# OSO-SCAP-A1-01.net
KiCad netlist of a schematic drawn in EAGLE
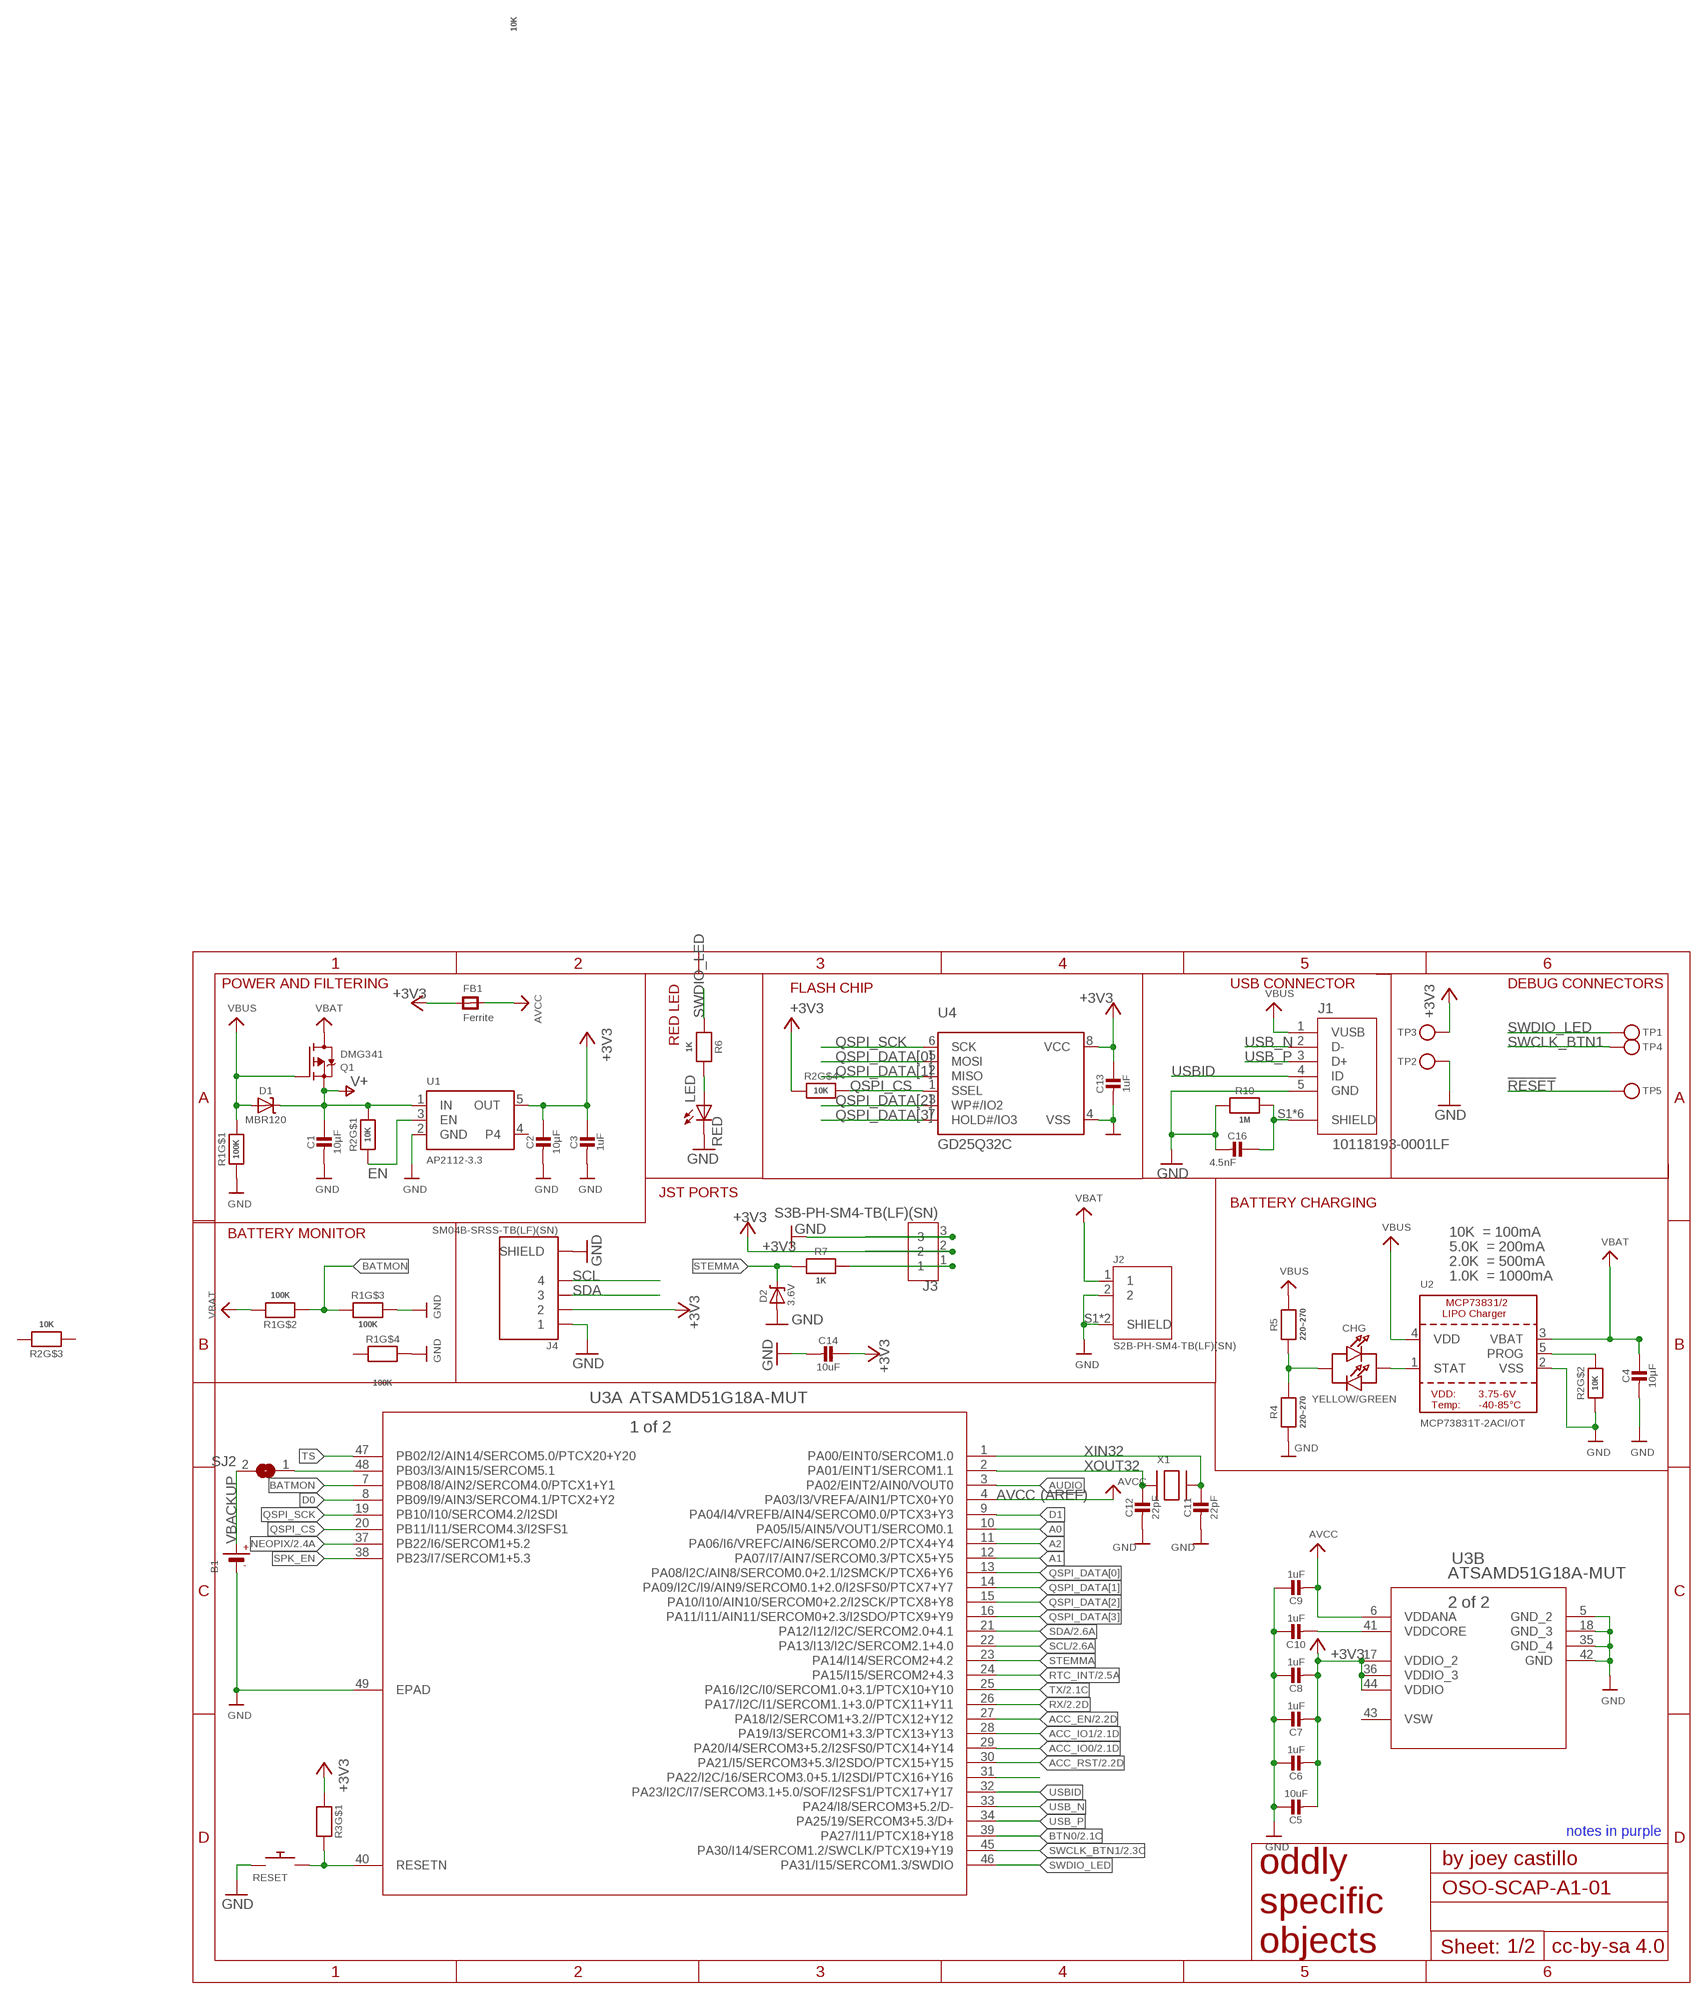
[diagram p0: schematic, sheet 1]
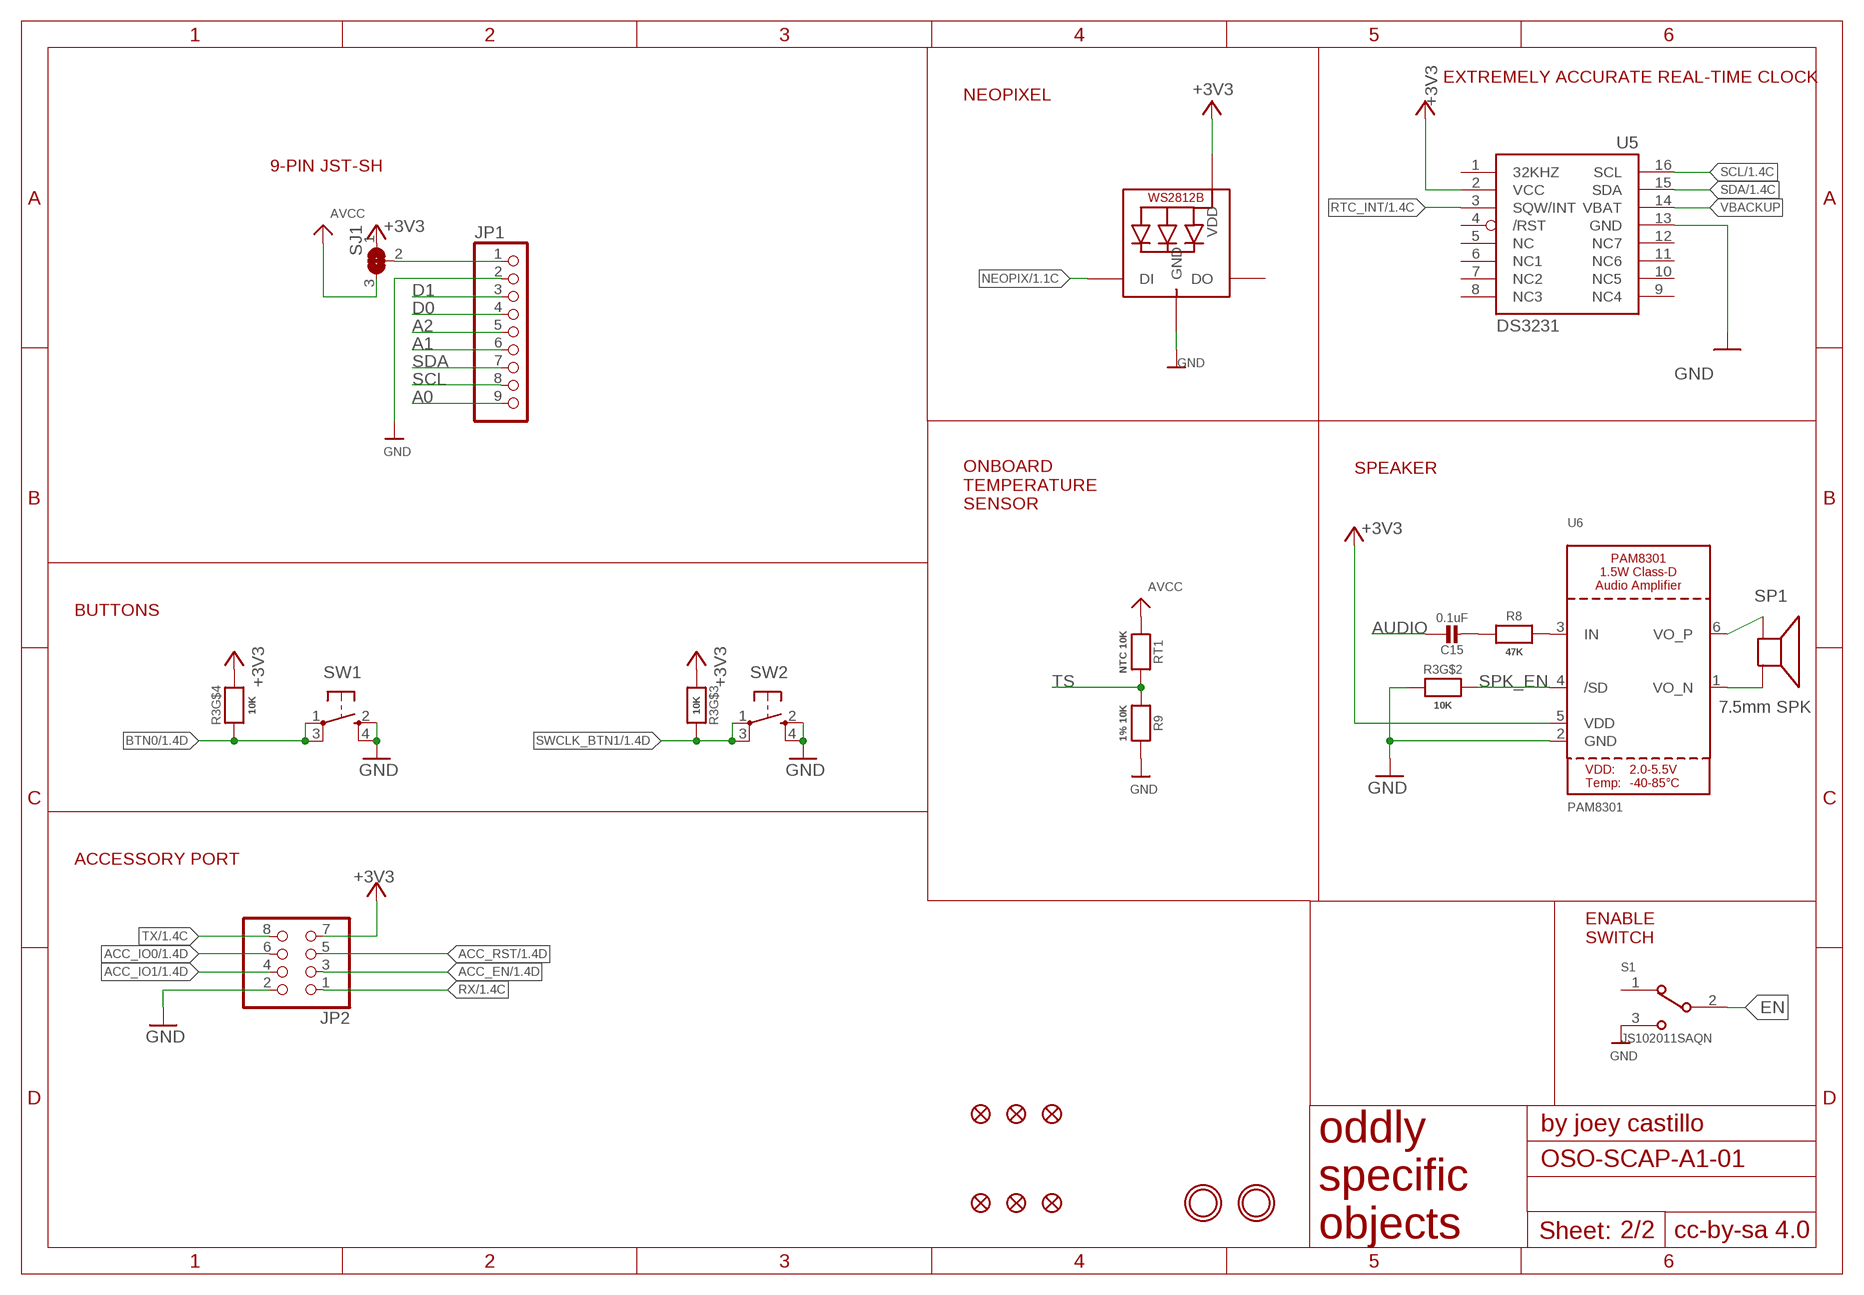
[diagram p1: schematic, sheet 2]

(export (version "E")
  (design (tool "Eeschema 10.0.6"))
  (components
    (comp (ref "C15")
      (value "0.1uF")
      (footprint "eagle-import:0805-NO")
      (libsource (lib "eagle-import") (part "CAP_CERAMIC0805-NOOUTLINE"))
    )
    (comp (ref "FID1")
      (value "FIDUCIAL_1MM")
      (footprint "eagle-import:FIDUCIAL_1MM")
      (libsource (lib "eagle-import") (part "FIDUCIAL_1MM"))
    )
    (comp (ref "FID2")
      (value "FIDUCIAL_1MM")
      (footprint "eagle-import:FIDUCIAL_1MM")
      (libsource (lib "eagle-import") (part "FIDUCIAL_1MM"))
    )
    (comp (ref "FID3")
      (value "FIDUCIAL_1MM")
      (footprint "eagle-import:FIDUCIAL_1MM")
      (libsource (lib "eagle-import") (part "FIDUCIAL_1MM"))
    )
    (comp (ref "FID4")
      (value "FIDUCIAL_1MM")
      (footprint "eagle-import:FIDUCIAL_1MM")
      (libsource (lib "eagle-import") (part "FIDUCIAL_1MM"))
    )
    (comp (ref "FID5")
      (value "FIDUCIAL_1MM")
      (footprint "eagle-import:FIDUCIAL_1MM")
      (libsource (lib "eagle-import") (part "FIDUCIAL_1MM"))
    )
    (comp (ref "FID6")
      (value "FIDUCIAL_1MM")
      (footprint "eagle-import:FIDUCIAL_1MM")
      (libsource (lib "eagle-import") (part "FIDUCIAL_1MM"))
    )
    (comp (ref "JP1")
      (value "HEADER-1X9_JSTSH")
      (footprint "eagle-import:JST_SH9")
      (libsource (lib "eagle-import") (part "HEADER-1X9_JSTSH"))
    )
    (comp (ref "JP2")
      (value "PINHD-2X4SMT")
      (footprint "eagle-import:PINHD_2X4_SMT")
      (libsource (lib "eagle-import") (part "PINHD-2X4SMT"))
    )
    (comp (ref "NEOPIX")
      (value "WS2812B_4020")
      (footprint "eagle-import:WS2812B_4020")
      (libsource (lib "eagle-import") (part "WS2812B_4020"))
    )
    (comp (ref "R3")
      (value "10K")
      (footprint "eagle-import:EXBV8V")
      (fields (field (name "MANUFACTURER_PART_NUMBER") "EXBV8V103JV"))
      (libsource (lib "eagle-import") (part "EXB-V8V103JV-GOOD"))
    )
    (comp (ref "R8")
      (value "47K")
      (footprint "eagle-import:0805-NO")
      (libsource (lib "eagle-import") (part "RESISTOR0805_NOOUTLINE"))
    )
    (comp (ref "R9")
      (value "1% 10K")
      (footprint "eagle-import:0805-NO")
      (libsource (lib "eagle-import") (part "RESISTOR0805_NOOUTLINE"))
    )
    (comp (ref "RT1")
      (value "NTC 10K")
      (footprint "eagle-import:0805-NO")
      (libsource (lib "eagle-import") (part "RESISTOR0805_NOOUTLINE"))
    )
    (comp (ref "S1")
      (value "JS102011SAQN")
      (footprint "eagle-import:SW_JS102011SAQN")
      (fields (field (name "DIGI-KEY_PART_NUMBER") "401-1999-1-ND") (field (name "MF") "C&K"))
      (libsource (lib "eagle-import") (part "JS102011SAQN"))
    )
    (comp (ref "SJ1")
      (value "SOLDERJUMPER_2WAY")
      (footprint "eagle-import:SOLDERJUMPER_2WAY_OPEN_NOPASTE")
      (libsource (lib "eagle-import") (part "SOLDERJUMPER_2WAY"))
    )
    (comp (ref "SP1")
      (value "7.5mm SPK")
      (footprint "eagle-import:BUZZER_SMT_5MM")
      (libsource (lib "eagle-import") (part "SPEAKER_BUZZER5MM"))
    )
    (comp (ref "SW1")
      (value "SPST_TACT-KMR2")
      (footprint "eagle-import:KMR2")
      (libsource (lib "eagle-import") (part "SPST_TACT-KMR2"))
    )
    (comp (ref "SW2")
      (value "SPST_TACT-KMR2")
      (footprint "eagle-import:KMR2")
      (libsource (lib "eagle-import") (part "SPST_TACT-KMR2"))
    )
    (comp (ref "U$1")
      (value "MOUNTINGHOLE2.5")
      (footprint "eagle-import:MOUNTINGHOLE_2.5_PLATED")
      (libsource (lib "eagle-import") (part "MOUNTINGHOLE2.5"))
    )
    (comp (ref "U$4")
      (value "MOUNTINGHOLE2.5")
      (footprint "eagle-import:MOUNTINGHOLE_2.5_PLATED")
      (libsource (lib "eagle-import") (part "MOUNTINGHOLE2.5"))
    )
    (comp (ref "U5")
      (value "DS3231/SO")
      (footprint "eagle-import:SO16W")
      (libsource (lib "eagle-import") (part "DS3231/SO"))
    )
    (comp (ref "U6")
      (value "PAM8301")
      (footprint "eagle-import:SOT23-6")
      (libsource (lib "eagle-import") (part "PAM8301"))
    )
    (comp (ref "B1")
      (value "CR1220")
      (footprint "eagle-import:CR1220-2")
      (libsource (lib "eagle-import") (part "BATTERYCR1220_2"))
    )
    (comp (ref "C1")
      (value "10µF")
      (footprint "eagle-import:0805-NO")
      (libsource (lib "eagle-import") (part "CAP_CERAMIC0805-NOOUTLINE"))
    )
    (comp (ref "C2")
      (value "10µF")
      (footprint "eagle-import:0805-NO")
      (libsource (lib "eagle-import") (part "CAP_CERAMIC0805-NOOUTLINE"))
    )
    (comp (ref "C3")
      (value "1uF")
      (footprint "eagle-import:0805-NO")
      (libsource (lib "eagle-import") (part "CAP_CERAMIC0805-NOOUTLINE"))
    )
    (comp (ref "C4")
      (value "10µF")
      (footprint "eagle-import:0805-NO")
      (libsource (lib "eagle-import") (part "CAP_CERAMIC0805-NOOUTLINE"))
    )
    (comp (ref "C5")
      (value "10uF")
      (footprint "eagle-import:0805_10MGAP")
      (libsource (lib "eagle-import") (part "CAP_CERAMIC0805_10MGAP"))
    )
    (comp (ref "C6")
      (value "1uF")
      (footprint "eagle-import:0805-NO")
      (libsource (lib "eagle-import") (part "CAP_CERAMIC0805-NOOUTLINE"))
    )
    (comp (ref "C7")
      (value "1uF")
      (footprint "eagle-import:0805-NO")
      (libsource (lib "eagle-import") (part "CAP_CERAMIC0805-NOOUTLINE"))
    )
    (comp (ref "C8")
      (value "1uF")
      (footprint "eagle-import:0805-NO")
      (libsource (lib "eagle-import") (part "CAP_CERAMIC0805-NOOUTLINE"))
    )
    (comp (ref "C9")
      (value "1uF")
      (footprint "eagle-import:0805_10MGAP")
      (libsource (lib "eagle-import") (part "CAP_CERAMIC0805_10MGAP"))
    )
    (comp (ref "C10")
      (value "1uF")
      (footprint "eagle-import:0805_10MGAP")
      (libsource (lib "eagle-import") (part "CAP_CERAMIC0805_10MGAP"))
    )
    (comp (ref "C11")
      (value "22pF")
      (footprint "eagle-import:0805-NO")
      (libsource (lib "eagle-import") (part "CAP_CERAMIC0805-NOOUTLINE"))
    )
    (comp (ref "C12")
      (value "22pF")
      (footprint "eagle-import:0805-NO")
      (libsource (lib "eagle-import") (part "CAP_CERAMIC0805-NOOUTLINE"))
    )
    (comp (ref "C13")
      (value "1uF")
      (footprint "eagle-import:0805-NO")
      (libsource (lib "eagle-import") (part "CAP_CERAMIC0805-NOOUTLINE"))
    )
    (comp (ref "C14")
      (value "10uF")
      (footprint "eagle-import:0805-NO")
      (libsource (lib "eagle-import") (part "CAP_CERAMIC0805-NOOUTLINE"))
    )
    (comp (ref "C16")
      (value "4.5nF")
      (footprint "eagle-import:0805-NO")
      (libsource (lib "eagle-import") (part "CAP_CERAMIC0805-NOOUTLINE"))
    )
    (comp (ref "CHG")
      (value "YELLOW/GREEN")
      (footprint "eagle-import:CHIPLED_1206")
      (libsource (lib "eagle-import") (part "LED_BIDI1206"))
    )
    (comp (ref "D1")
      (value "MBR120")
      (footprint "eagle-import:SOD-123")
      (libsource (lib "eagle-import") (part "DIODE-SCHOTTKYSOD-123"))
    )
    (comp (ref "D2")
      (value "3.6V")
      (footprint "eagle-import:SOD-123")
      (libsource (lib "eagle-import") (part "DIODE-ZENERSOD123"))
    )
    (comp (ref "FB1")
      (value "Ferrite")
      (footprint "eagle-import:_0805MP")
      (libsource (lib "eagle-import") (part "FERRITE_0805MP"))
    )
    (comp (ref "J1")
      (value "10118193-0001LF")
      (footprint "eagle-import:FCI_10118193-0001LF")
      (fields (field (name "DIGI-KEY_PART_NUMBER") "609-4616-1-ND") (field (name "MF") "Amphenol ICC"))
      (libsource (lib "eagle-import") (part "10118193-0001LF"))
    )
    (comp (ref "J2")
      (value "S2B-PH-SM4-TB(LF)(SN)")
      (footprint "eagle-import:JST_S2B-PH-SM4-TB(LF)(SN)")
      (fields
        (field (name "DIGI-KEY_PART_NUMBER") "455-1749-1-ND")
        (field (name "MF") "JST Sales")
        (field (name "MP") "S2B-PH-SM4-TB_LF__SN_")
      )
      (libsource (lib "eagle-import") (part "S2B-PH-SM4-TB(LF)(SN)"))
    )
    (comp (ref "J3")
      (value "S3B-PH-SM4-TB(LF)(SN)")
      (footprint "eagle-import:JST_S3B-PH-SM4-TB(LF)(SN)")
      (fields
        (field (name "DIGI-KEY_PART_NUMBER") "455-1750-1-ND")
        (field (name "MF") "JST Sales")
        (field (name "MP") "S3B-PH-SM4-TB_LF__SN_")
      )
      (libsource (lib "eagle-import") (part "S3B-PH-SM4-TB(LF)(SN)"))
    )
    (comp (ref "J4")
      (value "SM04B-SRSS-TB(LF)(SN)")
      (footprint "eagle-import:JST_SM04B-SRSS-TB(LF)(SN)")
      (fields
        (field (name "DIGI-KEY_PART_NUMBER") "455-1804-1-ND")
        (field (name "MF") "JST Sales")
        (field (name "MP") "SM04B-SRSS-TB_LF__SN_")
      )
      (libsource (lib "eagle-import") (part "SM04B-SRSS-TB(LF)(SN)"))
    )
    (comp (ref "LED")
      (value "RED")
      (footprint "eagle-import:CHIPLED_1206")
      (libsource (lib "eagle-import") (part "LEDCHIPLED_1206"))
    )
    (comp (ref "Q1")
      (value "DMG341")
      (footprint "eagle-import:SOT23-R")
      (libsource (lib "eagle-import") (part "MOSFET-P"))
    )
    (comp (ref "R1")
      (value "100K")
      (footprint "eagle-import:EXBV8V")
      (fields (field (name "MANUFACTURER_PART_NUMBER") "EXBV8V103JV"))
      (libsource (lib "eagle-import") (part "EXB-V8V103JV-GOOD"))
    )
    (comp (ref "R2")
      (value "10K")
      (footprint "eagle-import:EXBV8V")
      (fields (field (name "MANUFACTURER_PART_NUMBER") "EXBV8V103JV"))
      (libsource (lib "eagle-import") (part "EXB-V8V103JV-GOOD"))
    )
    (comp (ref "R4")
      (value "220~270")
      (footprint "eagle-import:0805-NO")
      (libsource (lib "eagle-import") (part "RESISTOR0805_NOOUTLINE"))
    )
    (comp (ref "R5")
      (value "220~270")
      (footprint "eagle-import:0805-NO")
      (libsource (lib "eagle-import") (part "RESISTOR0805_NOOUTLINE"))
    )
    (comp (ref "R6")
      (value "1K")
      (footprint "eagle-import:0805-NO")
      (libsource (lib "eagle-import") (part "RESISTOR0805_NOOUTLINE"))
    )
    (comp (ref "R7")
      (value "1K")
      (footprint "eagle-import:0805-NO")
      (libsource (lib "eagle-import") (part "RESISTOR0805_NOOUTLINE"))
    )
    (comp (ref "R10")
      (value "1M")
      (footprint "eagle-import:0805-NO")
      (libsource (lib "eagle-import") (part "RESISTOR0805_NOOUTLINE"))
    )
    (comp (ref "RESET")
      (value "SWITCH_PUSHBUTTONC&K_KSS")
      (footprint "eagle-import:BTN_CK_KSS")
      (libsource (lib "eagle-import") (part "SWITCH_PUSHBUTTONC&K_KSS"))
    )
    (comp (ref "SJ2")
      (value "SOLDERJUMPERREFLOW_NOPASTE")
      (footprint "eagle-import:SOLDERJUMPER_REFLOW_NOPASTE")
      (libsource (lib "eagle-import") (part "SOLDERJUMPERREFLOW_NOPASTE"))
    )
    (comp (ref "TP1")
      (value "TESTPOINTROUND1.5MMNO")
      (footprint "eagle-import:TESTPOINT_ROUND_1.5MM_NO")
      (libsource (lib "eagle-import") (part "TESTPOINTROUND1.5MMNO"))
    )
    (comp (ref "TP2")
      (value "TESTPOINTROUND1.5MMNO")
      (footprint "eagle-import:TESTPOINT_ROUND_1.5MM_NO")
      (libsource (lib "eagle-import") (part "TESTPOINTROUND1.5MMNO"))
    )
    (comp (ref "TP3")
      (value "TESTPOINTROUND1.5MMNO")
      (footprint "eagle-import:TESTPOINT_ROUND_1.5MM_NO")
      (libsource (lib "eagle-import") (part "TESTPOINTROUND1.5MMNO"))
    )
    (comp (ref "TP4")
      (value "TESTPOINTROUND1.5MMNO")
      (footprint "eagle-import:TESTPOINT_ROUND_1.5MM_NO")
      (libsource (lib "eagle-import") (part "TESTPOINTROUND1.5MMNO"))
    )
    (comp (ref "TP5")
      (value "TESTPOINTROUND1.5MMNO")
      (footprint "eagle-import:TESTPOINT_ROUND_1.5MM_NO")
      (libsource (lib "eagle-import") (part "TESTPOINTROUND1.5MMNO"))
    )
    (comp (ref "U1")
      (value "AP2112-3.3")
      (footprint "eagle-import:SOT23-5")
      (libsource (lib "eagle-import") (part "VREG_SOT23-5"))
    )
    (comp (ref "U2")
      (value "MCP73831T-2ACI/OT")
      (footprint "eagle-import:SOT23-5")
      (libsource (lib "eagle-import") (part "MCP73831/2"))
    )
    (comp (ref "U3")
      (value "ATSAMD51G18A-MUT")
      (footprint "eagle-import:QFN48_7X7MC")
      (fields (field (name "COPYRIGHT") "Copyright (C) 2018 Accelerated Designs. All rights reserved"))
      (libsource (lib "eagle-import") (part "ATSAMD51G18A-MUT"))
    )
    (comp (ref "U4")
      (value "GD25Q32C")
      (footprint "eagle-import:MICROBUILDER_SOIC8_150MIL")
      (libsource (lib "eagle-import") (part "MICROBUILDER_SPIFLASH_SOIC8"))
    )
    (comp (ref "X1")
      (value "XTAL-3.2X1.5")
      (footprint "eagle-import:XTAL3215")
      (libsource (lib "eagle-import") (part "XTAL-3.2X1.5"))
    )
  )
  (nets
    (net (code "1") (name "+3V3") (class "Default")
      (node (ref "C13") (pin "1") (pinfunction "1_1") (pintype "passive"))
      (node (ref "C14") (pin "1") (pinfunction "1_1") (pintype "passive"))
      (node (ref "C2") (pin "1") (pinfunction "1_1") (pintype "passive"))
      (node (ref "C3") (pin "1") (pinfunction "1_1") (pintype "passive"))
      (node (ref "C5") (pin "2") (pinfunction "2_2") (pintype "passive"))
      (node (ref "C6") (pin "2") (pinfunction "2_2") (pintype "passive"))
      (node (ref "C7") (pin "2") (pinfunction "2_2") (pintype "passive"))
      (node (ref "C8") (pin "2") (pinfunction "2_2") (pintype "passive"))
      (node (ref "FB1") (pin "1") (pinfunction "P$1_1") (pintype "passive"))
      (node (ref "J3") (pin "2") (pinfunction "2_2") (pintype "passive"))
      (node (ref "J4") (pin "2") (pinfunction "2_2") (pintype "passive"))
      (node (ref "JP2") (pin "7") (pinfunction "7_7") (pintype "passive"))
      (node (ref "NEOPIX") (pin "2") (pinfunction "VDD_2") (pintype "power_in"))
      (node (ref "R2") (pin "4") (pinfunction "1_4") (pintype "passive"))
      (node (ref "R3") (pin "1") (pinfunction "1_1") (pintype "passive"))
      (node (ref "R3") (pin "3") (pinfunction "1_3") (pintype "passive"))
      (node (ref "R3") (pin "5") (pinfunction "2_5") (pintype "passive"))
      (node (ref "SJ1") (pin "1") (pinfunction "1_1") (pintype "passive"))
      (node (ref "TP3") (pin "P$1") (pinfunction "P$1_P$1") (pintype "bidirectional"))
      (node (ref "U1") (pin "5") (pinfunction "OUT_5") (pintype "power_in"))
      (node (ref "U3") (pin "17") (pinfunction "VDDIO_2_17") (pintype "power_in"))
      (node (ref "U3") (pin "36") (pinfunction "VDDIO_3_36") (pintype "power_in"))
      (node (ref "U3") (pin "44") (pinfunction "VDDIO_44") (pintype "power_in"))
      (node (ref "U4") (pin "8") (pinfunction "VCC_8") (pintype "bidirectional"))
      (node (ref "U5") (pin "2") (pinfunction "VCC_2") (pintype "power_in"))
      (node (ref "U6") (pin "5") (pinfunction "VDD_5") (pintype "power_in"))
    )
    (net (code "2") (name "A0") (class "Default")
      (node (ref "JP1") (pin "9") (pinfunction "9_9") (pintype "passive"))
      (node (ref "U3") (pin "10") (pinfunction "PA05/I5/AIN5/VOUT1/SERCOM0.1_10") (pintype "bidirectional"))
    )
    (net (code "3") (name "A1") (class "Default")
      (node (ref "JP1") (pin "6") (pinfunction "6_6") (pintype "passive"))
      (node (ref "U3") (pin "12") (pinfunction "PA07/I7/AIN7/SERCOM0.3/PTCX5+Y5_12") (pintype "bidirectional"))
    )
    (net (code "4") (name "A2") (class "Default")
      (node (ref "JP1") (pin "5") (pinfunction "5_5") (pintype "passive"))
      (node (ref "U3") (pin "11") (pinfunction "PA06/I6/VREFC/AIN6/SERCOM0.2/PTCX4+Y4_11") (pintype "bidirectional"))
    )
    (net (code "5") (name "ACC_EN") (class "Default")
      (node (ref "JP2") (pin "3") (pinfunction "3_3") (pintype "passive"))
      (node (ref "U3") (pin "27") (pinfunction "PA18/I2/SERCOM1+3.2//PTCX12+Y12_27") (pintype "bidirectional"))
    )
    (net (code "6") (name "ACC_IO0") (class "Default")
      (node (ref "JP2") (pin "6") (pinfunction "6_6") (pintype "passive"))
      (node (ref "U3") (pin "29") (pinfunction "PA20/I4/SERCOM3+5.2/I2SFS0/PTCX14+Y14_29") (pintype "bidirectional"))
    )
    (net (code "7") (name "ACC_IO1") (class "Default")
      (node (ref "JP2") (pin "4") (pinfunction "4_4") (pintype "passive"))
      (node (ref "U3") (pin "28") (pinfunction "PA19/I3/SERCOM1+3.3/PTCX13+Y13_28") (pintype "bidirectional"))
    )
    (net (code "8") (name "ACC_RST") (class "Default")
      (node (ref "JP2") (pin "5") (pinfunction "5_5") (pintype "passive"))
      (node (ref "U3") (pin "30") (pinfunction "PA21/I5/SERCOM3+5.3/I2SDO/PTCX15+Y15_30") (pintype "bidirectional"))
    )
    (net (code "9") (name "AUDIO") (class "Default")
      (node (ref "C15") (pin "1") (pinfunction "1_1") (pintype "passive"))
      (node (ref "U3") (pin "3") (pinfunction "PA02/EINT2/AIN0/VOUT0_3") (pintype "bidirectional"))
    )
    (net (code "10") (name "AVCC") (class "Default")
      (node (ref "C9") (pin "2") (pinfunction "2_2") (pintype "passive"))
      (node (ref "FB1") (pin "2") (pinfunction "P$2_2") (pintype "passive"))
      (node (ref "RT1") (pin "1") (pinfunction "1_1") (pintype "passive"))
      (node (ref "SJ1") (pin "3") (pinfunction "3_3") (pintype "passive"))
      (node (ref "U3") (pin "4") (pinfunction "PA03/I3/VREFA/AIN1/PTCX0+Y0_4") (pintype "bidirectional"))
      (node (ref "U3") (pin "6") (pinfunction "VDDANA_6") (pintype "power_in"))
    )
    (net (code "11") (name "BATMON") (class "Default")
      (node (ref "R1") (pin "2") (pinfunction "1_2") (pintype "passive"))
      (node (ref "R1") (pin "3") (pinfunction "1_3") (pintype "passive"))
      (node (ref "U3") (pin "7") (pinfunction "PB08/I8/AIN2/SERCOM4.0/PTCX1+Y1_7") (pintype "bidirectional"))
    )
    (net (code "12") (name "BTN0") (class "Default")
      (node (ref "R3") (pin "4") (pinfunction "1_4") (pintype "passive"))
      (node (ref "SW1") (pin "1") (pinfunction "P_1") (pintype "passive"))
      (node (ref "SW1") (pin "3") (pinfunction "P1_3") (pintype "passive"))
      (node (ref "U3") (pin "39") (pinfunction "PA27/I11/PTCX18+Y18_39") (pintype "bidirectional"))
    )
    (net (code "13") (name "D0") (class "Default")
      (node (ref "JP1") (pin "4") (pinfunction "4_4") (pintype "passive"))
      (node (ref "U3") (pin "8") (pinfunction "PB09/I9/AIN3/SERCOM4.1/PTCX2+Y2_8") (pintype "bidirectional"))
    )
    (net (code "14") (name "D1") (class "Default")
      (node (ref "JP1") (pin "3") (pinfunction "3_3") (pintype "passive"))
      (node (ref "U3") (pin "9") (pinfunction "PA04/I4/VREFB/AIN4/SERCOM0.0/PTCX3+Y3_9") (pintype "bidirectional"))
    )
    (net (code "15") (name "EN") (class "Default")
      (node (ref "R2") (pin "1") (pinfunction "1_1") (pintype "passive"))
      (node (ref "S1") (pin "2") (pinfunction "2_2") (pintype "passive"))
      (node (ref "U1") (pin "3") (pinfunction "EN_3") (pintype "input"))
    )
    (net (code "16") (name "GND") (class "Default")
      (node (ref "B1") (pin "-") (pinfunction "-_-") (pintype "passive"))
      (node (ref "C1") (pin "2") (pinfunction "2_2") (pintype "passive"))
      (node (ref "C10") (pin "1") (pinfunction "1_1") (pintype "passive"))
      (node (ref "C11") (pin "2") (pinfunction "2_2") (pintype "passive"))
      (node (ref "C12") (pin "2") (pinfunction "2_2") (pintype "passive"))
      (node (ref "C13") (pin "2") (pinfunction "2_2") (pintype "passive"))
      (node (ref "C14") (pin "2") (pinfunction "2_2") (pintype "passive"))
      (node (ref "C16") (pin "2") (pinfunction "2_2") (pintype "passive"))
      (node (ref "C2") (pin "2") (pinfunction "2_2") (pintype "passive"))
      (node (ref "C3") (pin "2") (pinfunction "2_2") (pintype "passive"))
      (node (ref "C4") (pin "2") (pinfunction "2_2") (pintype "passive"))
      (node (ref "C5") (pin "1") (pinfunction "1_1") (pintype "passive"))
      (node (ref "C6") (pin "1") (pinfunction "1_1") (pintype "passive"))
      (node (ref "C7") (pin "1") (pinfunction "1_1") (pintype "passive"))
      (node (ref "C8") (pin "1") (pinfunction "1_1") (pintype "passive"))
      (node (ref "C9") (pin "1") (pinfunction "1_1") (pintype "passive"))
      (node (ref "D2") (pin "A") (pinfunction "A_A") (pintype "passive"))
      (node (ref "J1") (pin "5") (pinfunction "GND_5") (pintype "passive"))
      (node (ref "J2") (pin "2") (pinfunction "2_2") (pintype "passive"))
      (node (ref "J2") (pin "S1") (pinfunction "SHIELD_S1") (pintype "passive"))
      (node (ref "J2") (pin "S2") (pinfunction "SHIELD_S2") (pintype "passive"))
      (node (ref "J3") (pin "3") (pinfunction "3_3") (pintype "passive"))
      (node (ref "J4") (pin "1") (pinfunction "1_1") (pintype "passive"))
      (node (ref "J4") (pin "S1") (pinfunction "SHIELD_S1") (pintype "passive"))
      (node (ref "J4") (pin "S2") (pinfunction "SHIELD_S2") (pintype "passive"))
      (node (ref "JP1") (pin "2") (pinfunction "2_2") (pintype "passive"))
      (node (ref "JP2") (pin "2") (pinfunction "2_2") (pintype "passive"))
      (node (ref "LED") (pin "C") (pinfunction "C_C") (pintype "passive"))
      (node (ref "NEOPIX") (pin "4") (pinfunction "GND_4") (pintype "power_in"))
      (node (ref "R1") (pin "1") (pinfunction "1_1") (pintype "passive"))
      (node (ref "R1") (pin "5") (pinfunction "2_5") (pintype "passive"))
      (node (ref "R1") (pin "6") (pinfunction "2_6") (pintype "passive"))
      (node (ref "R10") (pin "2") (pinfunction "2_2") (pintype "passive"))
      (node (ref "R2") (pin "2") (pinfunction "1_2") (pintype "passive"))
      (node (ref "R3") (pin "2") (pinfunction "1_2") (pintype "passive"))
      (node (ref "R4") (pin "1") (pinfunction "1_1") (pintype "passive"))
      (node (ref "R9") (pin "2") (pinfunction "2_2") (pintype "passive"))
      (node (ref "RESET") (pin "P$1") (pinfunction "P$1_P$1") (pintype "passive"))
      (node (ref "S1") (pin "3") (pinfunction "3_3") (pintype "passive"))
      (node (ref "SW1") (pin "2") (pinfunction "S_2") (pintype "passive"))
      (node (ref "SW1") (pin "4") (pinfunction "S1_4") (pintype "passive"))
      (node (ref "SW2") (pin "2") (pinfunction "S_2") (pintype "passive"))
      (node (ref "SW2") (pin "4") (pinfunction "S1_4") (pintype "passive"))
      (node (ref "TP2") (pin "P$1") (pinfunction "P$1_P$1") (pintype "bidirectional"))
      (node (ref "U1") (pin "2") (pinfunction "GND_2") (pintype "power_in"))
      (node (ref "U2") (pin "2") (pinfunction "VSS_2") (pintype "power_in"))
      (node (ref "U3") (pin "18") (pinfunction "GND_3_18") (pintype "passive"))
      (node (ref "U3") (pin "35") (pinfunction "GND_4_35") (pintype "passive"))
      (node (ref "U3") (pin "42") (pinfunction "GND_42") (pintype "passive"))
      (node (ref "U3") (pin "49") (pinfunction "EPAD_49") (pintype "passive"))
      (node (ref "U3") (pin "5") (pinfunction "GND_2_5") (pintype "passive"))
      (node (ref "U4") (pin "4") (pinfunction "VSS_4") (pintype "bidirectional"))
      (node (ref "U5") (pin "13") (pinfunction "GND_13") (pintype "power_in"))
      (node (ref "U6") (pin "2") (pinfunction "GND_2") (pintype "power_in"))
    )
    (net (code "17") (name "NEOPIX") (class "Default")
      (node (ref "NEOPIX") (pin "1") (pinfunction "DI_1") (pintype "input"))
      (node (ref "U3") (pin "37") (pinfunction "PB22/I6/SERCOM1+5.2_37") (pintype "bidirectional"))
    )
    (net (code "18") (name "Net-(C15-Pad2)") (class "Default")
      (node (ref "C15") (pin "2") (pinfunction "2_2") (pintype "passive"))
      (node (ref "R8") (pin "1") (pinfunction "1_1") (pintype "passive"))
    )
    (net (code "19") (name "Net-(C16-Pad1)") (class "Default")
      (node (ref "C16") (pin "1") (pinfunction "1_1") (pintype "passive"))
      (node (ref "J1") (pin "S1") (pinfunction "SHIELD_S1") (pintype "passive"))
      (node (ref "J1") (pin "S2") (pinfunction "SHIELD_S2") (pintype "passive"))
      (node (ref "J1") (pin "S3") (pinfunction "SHIELD_S3") (pintype "passive"))
      (node (ref "J1") (pin "S4") (pinfunction "SHIELD_S4") (pintype "passive"))
      (node (ref "J1") (pin "S5") (pinfunction "SHIELD_S5") (pintype "passive"))
      (node (ref "J1") (pin "S6") (pinfunction "SHIELD_S6") (pintype "passive"))
      (node (ref "R10") (pin "1") (pinfunction "1_1") (pintype "passive"))
    )
    (net (code "20") (name "Net-(CHG-PadA)") (class "Default")
      (node (ref "CHG") (pin "A") (pinfunction "A_A") (pintype "passive"))
      (node (ref "R4") (pin "2") (pinfunction "2_2") (pintype "passive"))
      (node (ref "R5") (pin "1") (pinfunction "1_1") (pintype "passive"))
    )
    (net (code "21") (name "Net-(J3-Pad1)") (class "Default")
      (node (ref "J3") (pin "1") (pinfunction "1_1") (pintype "passive"))
      (node (ref "R7") (pin "1") (pinfunction "1_1") (pintype "passive"))
    )
    (net (code "22") (name "Net-(JP1-Pad1)") (class "Default")
      (node (ref "JP1") (pin "1") (pinfunction "1_1") (pintype "passive"))
      (node (ref "SJ1") (pin "2") (pinfunction "2_2") (pintype "passive"))
    )
    (net (code "23") (name "Net-(LED-PadA)") (class "Default")
      (node (ref "LED") (pin "A") (pinfunction "A_A") (pintype "passive"))
      (node (ref "R6") (pin "2") (pinfunction "2_2") (pintype "passive"))
    )
    (net (code "24") (name "Net-(R2B-2)") (class "Default")
      (node (ref "R2") (pin "7") (pinfunction "2_7") (pintype "passive"))
      (node (ref "U2") (pin "5") (pinfunction "PROG_5") (pintype "input"))
    )
    (net (code "25") (name "Net-(U2-STAT)") (class "Default")
      (node (ref "CHG") (pin "C") (pinfunction "C_C") (pintype "passive"))
      (node (ref "U2") (pin "1") (pinfunction "STAT_1") (pintype "output"))
    )
    (net (code "26") (name "Net-(U3A-PB03{slash}I3{slash}AIN15{slash}SERCOM5.1)") (class "Default")
      (node (ref "SJ2") (pin "1") (pinfunction "1_1") (pintype "passive"))
      (node (ref "U3") (pin "48") (pinfunction "PB03/I3/AIN15/SERCOM5.1_48") (pintype "bidirectional"))
    )
    (net (code "27") (name "Net-(U3B-VDDCORE)") (class "Default")
      (node (ref "C10") (pin "2") (pinfunction "2_2") (pintype "passive"))
      (node (ref "U3") (pin "41") (pinfunction "VDDCORE_41") (pintype "bidirectional"))
    )
    (net (code "28") (name "Net-(U6-IN)") (class "Default")
      (node (ref "R8") (pin "2") (pinfunction "2_2") (pintype "passive"))
      (node (ref "U6") (pin "3") (pinfunction "IN_3") (pintype "input"))
    )
    (net (code "29") (name "Net-(U6-VO_N)") (class "Default")
      (node (ref "SP1") (pin "+") (pinfunction "+_+") (pintype "passive"))
      (node (ref "U6") (pin "1") (pinfunction "VO_N_1") (pintype "output"))
    )
    (net (code "30") (name "Net-(U6-VO_P)") (class "Default")
      (node (ref "SP1") (pin "-") (pinfunction "-_-") (pintype "passive"))
      (node (ref "U6") (pin "6") (pinfunction "VO_P_6") (pintype "output"))
    )
    (net (code "31") (name "QSPI_CS") (class "Default")
      (node (ref "R2") (pin "5") (pinfunction "2_5") (pintype "passive"))
      (node (ref "U3") (pin "20") (pinfunction "PB11/I11/SERCOM4.3/I2SFS1_20") (pintype "bidirectional"))
      (node (ref "U4") (pin "1") (pinfunction "SSEL_1") (pintype "bidirectional"))
    )
    (net (code "32") (name "QSPI_DATA[0]") (class "Default")
      (node (ref "U3") (pin "13") (pinfunction "PA08/I2C/AIN8/SERCOM0.0+2.1/I2SMCK/PTCX6+Y6_13") (pintype "bidirectional"))
      (node (ref "U4") (pin "5") (pinfunction "MOSI_5") (pintype "bidirectional"))
    )
    (net (code "33") (name "QSPI_DATA[1]") (class "Default")
      (node (ref "U3") (pin "14") (pinfunction "PA09/I2C/I9/AIN9/SERCOM0.1+2.0/I2SFS0/PTCX7+Y7_14") (pintype "bidirectional"))
      (node (ref "U4") (pin "2") (pinfunction "MISO_2") (pintype "bidirectional"))
    )
    (net (code "34") (name "QSPI_DATA[2]") (class "Default")
      (node (ref "U3") (pin "15") (pinfunction "PA10/I10/AIN10/SERCOM0+2.2/I2SCK/PTCX8+Y8_15") (pintype "bidirectional"))
      (node (ref "U4") (pin "3") (pinfunction "WP#/IO2_3") (pintype "bidirectional"))
    )
    (net (code "35") (name "QSPI_DATA[3]") (class "Default")
      (node (ref "U3") (pin "16") (pinfunction "PA11/I11/AIN11/SERCOM0+2.3/I2SDO/PTCX9+Y9_16") (pintype "bidirectional"))
      (node (ref "U4") (pin "7") (pinfunction "HOLD#/IO3_7") (pintype "bidirectional"))
    )
    (net (code "36") (name "QSPI_SCK") (class "Default")
      (node (ref "U3") (pin "19") (pinfunction "PB10/I10/SERCOM4.2/I2SDI_19") (pintype "bidirectional"))
      (node (ref "U4") (pin "6") (pinfunction "SCK_6") (pintype "bidirectional"))
    )
    (net (code "37") (name "RTC_INT") (class "Default")
      (node (ref "U3") (pin "24") (pinfunction "PA15/I15/SERCOM2+4.3_24") (pintype "bidirectional"))
      (node (ref "U5") (pin "3") (pinfunction "SQW/INT_3") (pintype "output"))
    )
    (net (code "38") (name "RX") (class "Default")
      (node (ref "JP2") (pin "1") (pinfunction "1_1") (pintype "passive"))
      (node (ref "U3") (pin "26") (pinfunction "PA17/I2C/I1/SERCOM1.1+3.0/PTCX11+Y11_26") (pintype "bidirectional"))
    )
    (net (code "39") (name "SCL") (class "Default")
      (node (ref "J4") (pin "4") (pinfunction "4_4") (pintype "passive"))
      (node (ref "JP1") (pin "8") (pinfunction "8_8") (pintype "passive"))
      (node (ref "U3") (pin "22") (pinfunction "PA13/I13/I2C/SERCOM2.1+4.0_22") (pintype "bidirectional"))
      (node (ref "U5") (pin "16") (pinfunction "SCL_16") (pintype "bidirectional"))
    )
    (net (code "40") (name "SDA") (class "Default")
      (node (ref "J4") (pin "3") (pinfunction "3_3") (pintype "passive"))
      (node (ref "JP1") (pin "7") (pinfunction "7_7") (pintype "passive"))
      (node (ref "U3") (pin "21") (pinfunction "PA12/I12/I2C/SERCOM2.0+4.1_21") (pintype "bidirectional"))
      (node (ref "U5") (pin "15") (pinfunction "SDA_15") (pintype "bidirectional"))
    )
    (net (code "41") (name "SPK_EN") (class "Default")
      (node (ref "R3") (pin "7") (pinfunction "2_7") (pintype "passive"))
      (node (ref "U3") (pin "38") (pinfunction "PB23/I7/SERCOM1+5.3_38") (pintype "bidirectional"))
      (node (ref "U6") (pin "4") (pinfunction "/SD_4") (pintype "input"))
    )
    (net (code "42") (name "STEMMA") (class "Default")
      (node (ref "D2") (pin "C") (pinfunction "C_C") (pintype "passive"))
      (node (ref "R7") (pin "2") (pinfunction "2_2") (pintype "passive"))
      (node (ref "U3") (pin "23") (pinfunction "PA14/I14/SERCOM2+4.2_23") (pintype "bidirectional"))
    )
    (net (code "43") (name "SWCLK_BTN1") (class "Default")
      (node (ref "R3") (pin "6") (pinfunction "2_6") (pintype "passive"))
      (node (ref "SW2") (pin "1") (pinfunction "P_1") (pintype "passive"))
      (node (ref "SW2") (pin "3") (pinfunction "P1_3") (pintype "passive"))
      (node (ref "TP4") (pin "P$1") (pinfunction "P$1_P$1") (pintype "bidirectional"))
      (node (ref "U3") (pin "45") (pinfunction "PA30/I14/SERCOM1.2/SWCLK/PTCX19+Y19_45") (pintype "bidirectional"))
    )
    (net (code "44") (name "SWDIO_LED") (class "Default")
      (node (ref "R6") (pin "1") (pinfunction "1_1") (pintype "passive"))
      (node (ref "TP1") (pin "P$1") (pinfunction "P$1_P$1") (pintype "bidirectional"))
      (node (ref "U3") (pin "46") (pinfunction "PA31/I15/SERCOM1.3/SWDIO_46") (pintype "bidirectional"))
    )
    (net (code "45") (name "TS") (class "Default")
      (node (ref "R9") (pin "1") (pinfunction "1_1") (pintype "passive"))
      (node (ref "RT1") (pin "2") (pinfunction "2_2") (pintype "passive"))
      (node (ref "U3") (pin "47") (pinfunction "PB02/I2/AIN14/SERCOM5.0/PTCX20+Y20_47") (pintype "bidirectional"))
    )
    (net (code "46") (name "TX") (class "Default")
      (node (ref "JP2") (pin "8") (pinfunction "8_8") (pintype "passive"))
      (node (ref "U3") (pin "25") (pinfunction "PA16/I2C/I0/SERCOM1.0+3.1/PTCX10+Y10_25") (pintype "bidirectional"))
    )
    (net (code "47") (name "USBID") (class "Default")
      (node (ref "J1") (pin "4") (pinfunction "ID_4") (pintype "passive"))
      (node (ref "U3") (pin "32") (pinfunction "PA23/I2C/I7/SERCOM3.1+5.0/SOF/I2SFS1/PTCX17+Y17_32") (pintype "bidirectional"))
    )
    (net (code "48") (name "USB_N") (class "Default")
      (node (ref "J1") (pin "2") (pinfunction "D-_2") (pintype "passive"))
      (node (ref "U3") (pin "33") (pinfunction "PA24/I8/SERCOM3+5.2/D-_33") (pintype "bidirectional"))
    )
    (net (code "49") (name "USB_P") (class "Default")
      (node (ref "J1") (pin "3") (pinfunction "D+_3") (pintype "passive"))
      (node (ref "U3") (pin "34") (pinfunction "PA25/19/SERCOM3+5.3/D+_34") (pintype "bidirectional"))
    )
    (net (code "50") (name "V+") (class "Default")
      (node (ref "C1") (pin "1") (pinfunction "1_1") (pintype "passive"))
      (node (ref "D1") (pin "C") (pinfunction "C_C") (pintype "passive"))
      (node (ref "Q1") (pin "2") (pinfunction "S_2") (pintype "passive"))
      (node (ref "R2") (pin "8") (pinfunction "2_8") (pintype "passive"))
      (node (ref "U1") (pin "1") (pinfunction "IN_1") (pintype "power_in"))
    )
    (net (code "51") (name "VBACKUP") (class "Default")
      (node (ref "B1") (pin "+") (pinfunction "+_+") (pintype "passive"))
      (node (ref "SJ2") (pin "2") (pinfunction "2_2") (pintype "passive"))
      (node (ref "U5") (pin "14") (pinfunction "VBAT_14") (pintype "power_in"))
    )
    (net (code "52") (name "VBAT") (class "Default")
      (node (ref "C4") (pin "1") (pinfunction "1_1") (pintype "passive"))
      (node (ref "J2") (pin "1") (pinfunction "1_1") (pintype "passive"))
      (node (ref "Q1") (pin "3") (pinfunction "D_3") (pintype "passive"))
      (node (ref "R1") (pin "7") (pinfunction "2_7") (pintype "passive"))
      (node (ref "U2") (pin "3") (pinfunction "VBAT_3") (pintype "power_in"))
    )
    (net (code "53") (name "VBUS") (class "Default")
      (node (ref "D1") (pin "A") (pinfunction "A_A") (pintype "passive"))
      (node (ref "J1") (pin "1") (pinfunction "VUSB_1") (pintype "passive"))
      (node (ref "Q1") (pin "1") (pinfunction "G_1") (pintype "passive"))
      (node (ref "R1") (pin "8") (pinfunction "2_8") (pintype "passive"))
      (node (ref "R5") (pin "2") (pinfunction "2_2") (pintype "passive"))
      (node (ref "U2") (pin "4") (pinfunction "VDD_4") (pintype "power_in"))
    )
    (net (code "54") (name "VSW") (class "Default")
      (node (ref "U3") (pin "43") (pinfunction "VSW_43") (pintype "power_in"))
    )
    (net (code "55") (name "XIN32") (class "Default")
      (node (ref "C11") (pin "1") (pinfunction "1_1") (pintype "passive"))
      (node (ref "U3") (pin "1") (pinfunction "PA00/EINT0/SERCOM1.0_1") (pintype "bidirectional"))
      (node (ref "X1") (pin "P$2") (pinfunction "P$2_P$2") (pintype "bidirectional"))
    )
    (net (code "56") (name "XOUT32") (class "Default")
      (node (ref "C12") (pin "1") (pinfunction "1_1") (pintype "passive"))
      (node (ref "U3") (pin "2") (pinfunction "PA01/EINT1/SERCOM1.1_2") (pintype "bidirectional"))
      (node (ref "X1") (pin "P$1") (pinfunction "P$1_P$1") (pintype "bidirectional"))
    )
    (net (code "57") (name "unconnected-(NEOPIX-DO-Pad3)") (class "Default")
      (node (ref "NEOPIX") (pin "3") (pinfunction "DO_3") (pintype "output"))
    )
    (net (code "58") (name "unconnected-(R1D-1-Pad4)") (class "Default")
      (node (ref "R1") (pin "4") (pinfunction "1_4") (pintype "passive"))
    )
    (net (code "59") (name "unconnected-(R2C-1-Pad3)") (class "Default")
      (node (ref "R2") (pin "3") (pinfunction "1_3") (pintype "passive"))
    )
    (net (code "60") (name "unconnected-(R2C-2-Pad6)") (class "Default")
      (node (ref "R2") (pin "6") (pinfunction "2_6") (pintype "passive"))
    )
    (net (code "61") (name "unconnected-(S1-Pad1)") (class "Default")
      (node (ref "S1") (pin "1") (pinfunction "1_1") (pintype "passive"))
    )
    (net (code "62") (name "unconnected-(U1-P4-Pad4)") (class "Default")
      (node (ref "U1") (pin "4") (pinfunction "P4_4") (pintype "bidirectional"))
    )
    (net (code "63") (name "unconnected-(U3A-PA22{slash}I2C{slash}16{slash}SERCOM3.0+5.1{slash}I2SDI{slash}PTCX16+Y16-Pad31)") (class "Default")
      (node (ref "U3") (pin "31") (pinfunction "PA22/I2C/16/SERCOM3.0+5.1/I2SDI/PTCX16+Y16_31") (pintype "bidirectional"))
    )
    (net (code "64") (name "unconnected-(U5-32KHZ-Pad1)") (class "Default")
      (node (ref "U5") (pin "1") (pinfunction "32KHZ_1") (pintype "output"))
    )
    (net (code "65") (name "unconnected-(U5-NC-Pad5)") (class "Default")
      (node (ref "U5") (pin "5") (pinfunction "NC_5") (pintype "no_connect"))
    )
    (net (code "66") (name "unconnected-(U5-NC1-Pad6)") (class "Default")
      (node (ref "U5") (pin "6") (pinfunction "NC1_6") (pintype "no_connect"))
    )
    (net (code "67") (name "unconnected-(U5-NC2-Pad7)") (class "Default")
      (node (ref "U5") (pin "7") (pinfunction "NC2_7") (pintype "no_connect"))
    )
    (net (code "68") (name "unconnected-(U5-NC3-Pad8)") (class "Default")
      (node (ref "U5") (pin "8") (pinfunction "NC3_8") (pintype "no_connect"))
    )
    (net (code "69") (name "unconnected-(U5-NC4-Pad9)") (class "Default")
      (node (ref "U5") (pin "9") (pinfunction "NC4_9") (pintype "no_connect"))
    )
    (net (code "70") (name "unconnected-(U5-NC5-Pad10)") (class "Default")
      (node (ref "U5") (pin "10") (pinfunction "NC5_10") (pintype "no_connect"))
    )
    (net (code "71") (name "unconnected-(U5-NC6-Pad11)") (class "Default")
      (node (ref "U5") (pin "11") (pinfunction "NC6_11") (pintype "no_connect"))
    )
    (net (code "72") (name "unconnected-(U5-NC7-Pad12)") (class "Default")
      (node (ref "U5") (pin "12") (pinfunction "NC7_12") (pintype "no_connect"))
    )
    (net (code "73") (name "unconnected-(U5-{slash}RST-Pad4)") (class "Default")
      (node (ref "U5") (pin "4") (pinfunction "/RST_4") (pintype "passive"))
    )
    (net (code "74") (name "~{RESET}") (class "Default")
      (node (ref "R3") (pin "8") (pinfunction "2_8") (pintype "passive"))
      (node (ref "RESET") (pin "P$2") (pinfunction "P$2_P$2") (pintype "passive"))
      (node (ref "TP5") (pin "P$1") (pinfunction "P$1_P$1") (pintype "bidirectional"))
      (node (ref "U3") (pin "40") (pinfunction "RESETN_40") (pintype "passive"))
    )
  )
)
